# Bridge_Rectifier.net
KiCad netlist of a schematic drawn in Altium Designer
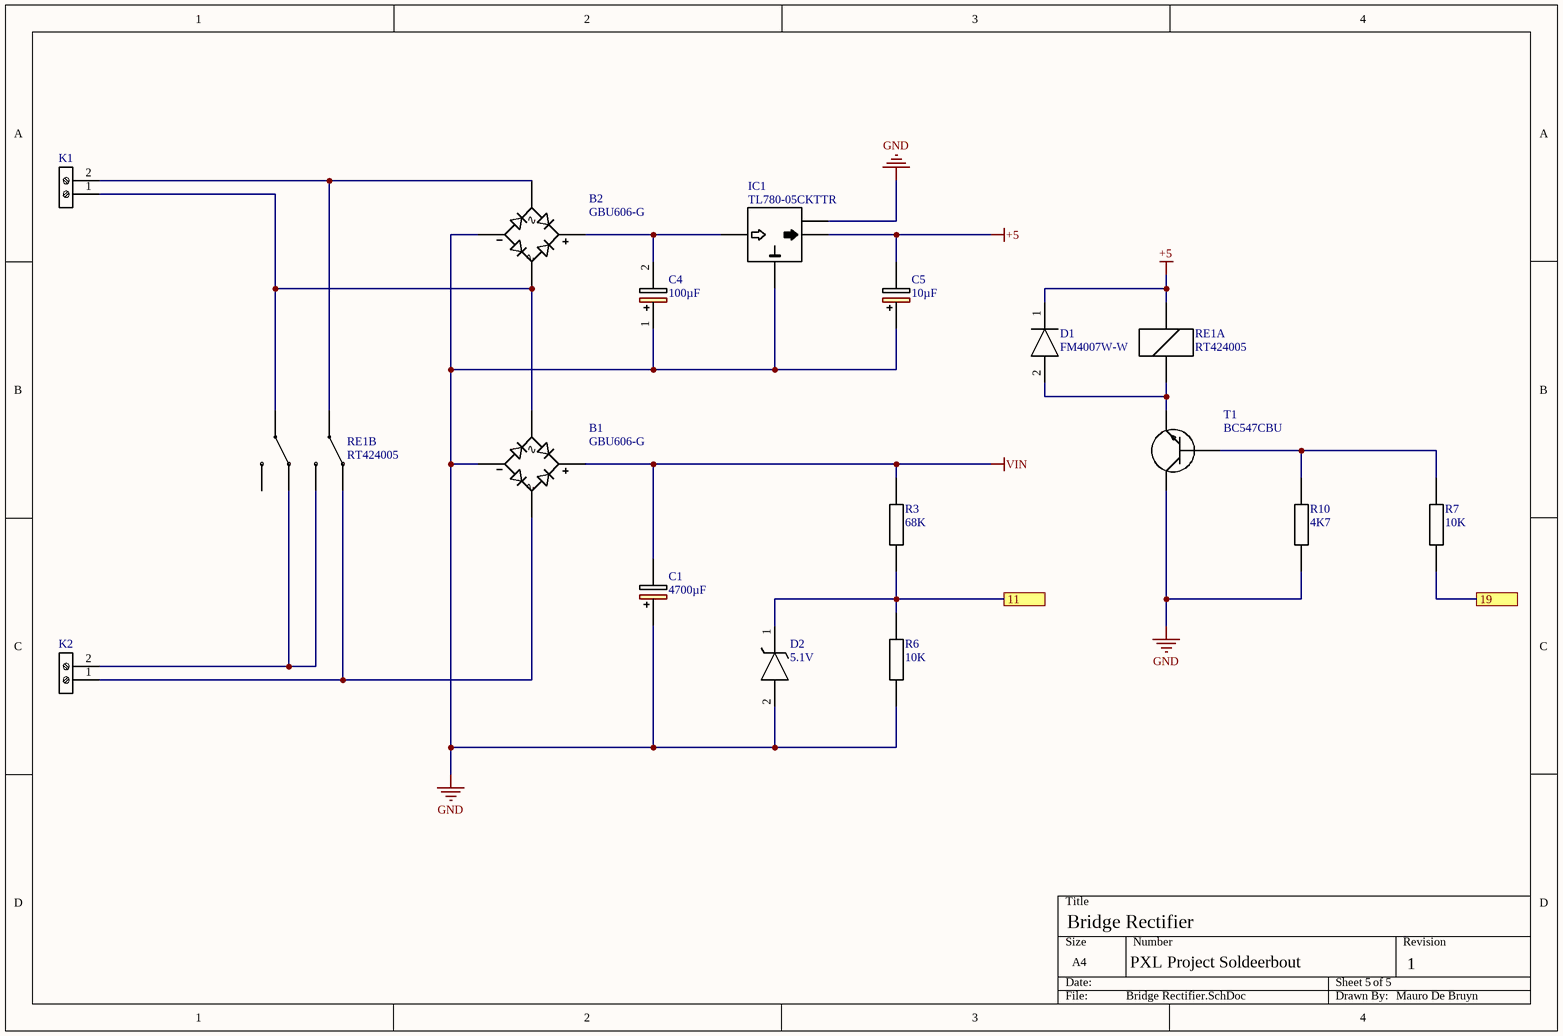
[diagram p0: Bridge Rectifier.SchDoc]

(export (version "E")
  (design (tool "Eeschema 10.0.6"))
  (components
    (comp (ref "B1")
      (value "GBU606-G")
      (footprint "SamacSys:GBU606G")
      (description "Bridge Rectifier")
      (libsource (lib "SamacSys") (part "GBU606-G"))
    )
    (comp (ref "B2")
      (value "GBU606-G")
      (footprint "SamacSys:GBU606G")
      (description "Bridge Rectifier")
      (libsource (lib "SamacSys") (part "GBU606-G"))
    )
    (comp (ref "C1")
      (value "4700µF")
      (footprint "SamacSys:CAPPRD750W80D1850H4150")
      (description "Capacitor Polarised")
      (fields
        (field (name "MOUSER2 PART NUMBER") "232-50PK4700MEFC18X4")
        (field (name "MANUFACTURER_PART_NUMBER") "50PK4700MEFC18X40")
      )
      (libsource (lib "SamacSys") (part "50PK4700MEFC18X40"))
    )
    (comp (ref "C4")
      (value "100µF")
      (footprint "SamacSys:CAPPRD350W60D825H1300")
      (description "Capacitor Polarised")
      (fields (field (name "MANUFACTURER_PART_NUMBER") "RGA101M1HBK-0811G"))
      (libsource (lib "SamacSys") (part "RGA101M1HBK-0811G"))
    )
    (comp (ref "C5")
      (value "10µF")
      (footprint "SamacSys:CAPPRD200W52D500H1250")
      (description "Capacitor Polarised")
      (fields
        (field (name "MOUSER2 PART NUMBER") "710-860020672010")
        (field (name "MANUFACTURER_PART_NUMBER") "860020672010")
      )
      (libsource (lib "SamacSys") (part "860020672010"))
    )
    (comp (ref "D1")
      (value "FM4007W-W")
      (footprint "SamacSys:DIOM5025X231N")
      (description "Bridge Rectifier")
      (fields (field (name "MOUSER2 PART NUMBER") "583-FM4007W-W"))
      (libsource (lib "SamacSys") (part "FM4007W-W"))
    )
    (comp (ref "D2")
      (value "5.1V")
      (footprint "SamacSys:SOD3716X135N")
      (description "Zener Diode")
      (fields
        (field (name "MOUSER2 PART NUMBER") "863-MMSZ4689T1G")
        (field (name "MANUFACTURER_PART_NUMBER") "MMSZ4689T1G")
      )
      (libsource (lib "SamacSys") (part "MMSZ4689T1G"))
    )
    (comp (ref "IC1")
      (value "TL780-05CKTTR")
      (footprint "SamacSys:TL78005CKTTR")
      (description "Integrated Circuit")
      (libsource (lib "SamacSys") (part "TL780-05CKTTR"))
    )
    (comp (ref "K1")
      (value "2 Pin Connector 1716020000")
      (footprint "SamacSys:1716020000")
      (description "Connector")
      (fields (field (name "MANUFACTURER_PART_NUMBER") "1716020000"))
      (libsource (lib "SamacSys") (part "2 Pin Connector 1716020000"))
    )
    (comp (ref "K2")
      (value "2 Pin Connector 1716020000")
      (footprint "SamacSys:1716020000")
      (description "Connector")
      (fields (field (name "MANUFACTURER_PART_NUMBER") "1716020000"))
      (libsource (lib "SamacSys") (part "2 Pin Connector 1716020000"))
    )
    (comp (ref "R3")
      (value "68K")
      (footprint "SamacSys:C0805")
      (description "Resistor")
      (fields (field (name "MANUFACTURER_PART_NUMBER") "C0805C391G3GACTU"))
      (libsource (lib "SamacSys") (part "0805"))
    )
    (comp (ref "R6")
      (value "10K")
      (footprint "SamacSys:C0805")
      (description "Resistor")
      (fields (field (name "MANUFACTURER_PART_NUMBER") "C0805C391G3GACTU"))
      (libsource (lib "SamacSys") (part "0805"))
    )
    (comp (ref "R7")
      (value "10K")
      (footprint "SamacSys:C0805")
      (description "Resistor")
      (fields (field (name "MANUFACTURER_PART_NUMBER") "C0805C391G3GACTU"))
      (libsource (lib "SamacSys") (part "0805"))
    )
    (comp (ref "R10")
      (value "4K7")
      (footprint "SamacSys:C0805")
      (description "Resistor")
      (fields (field (name "MANUFACTURER_PART_NUMBER") "C0805C391G3GACTU"))
      (libsource (lib "SamacSys") (part "0805"))
    )
    (comp (ref "RE1")
      (value "RT424005")
      (footprint "SamacSys:RT42")
      (description "Relay or Contactor")
      (fields (field (name "MOUSER2 PART NUMBER") "655-RT424005"))
      (libsource (lib "SamacSys") (part "RT424005"))
    )
    (comp (ref "T1")
      (value "BC547CBU")
      (footprint "SamacSys:BC547CBU")
      (description "Transistor BJT NPN")
      (libsource (lib "SamacSys") (part "BC547CBU"))
    )
  )
  (nets
    (net (code "1") (name "+5") (class "Default")
      (node (ref "C5") (pin "2") (pinfunction "-_2") (pintype "passive"))
      (node (ref "D1") (pin "1") (pinfunction "K_1") (pintype "passive"))
      (node (ref "IC1") (pin "3") (pinfunction "OUTPUT_3") (pintype "passive"))
      (node (ref "RE1") (pin "1") (pinfunction "A1_COIL_1") (pintype "passive"))
    )
    (net (code "2") (name "/11") (class "Default")
      (node (ref "D2") (pin "1") (pinfunction "K_1") (pintype "passive"))
      (node (ref "R3") (pin "1") (pinfunction "1_1") (pintype "passive"))
      (node (ref "R6") (pin "2") (pinfunction "2_2") (pintype "passive"))
    )
    (net (code "3") (name "/19") (class "Default")
      (node (ref "R7") (pin "1") (pinfunction "1_1") (pintype "passive"))
    )
    (net (code "4") (name "GND") (class "Default")
      (node (ref "B1") (pin "4") (pinfunction "-_4") (pintype "passive"))
      (node (ref "B2") (pin "4") (pinfunction "-_4") (pintype "passive"))
      (node (ref "C1") (pin "1") (pinfunction "+_1") (pintype "passive"))
      (node (ref "C4") (pin "1") (pinfunction "+_1") (pintype "passive"))
      (node (ref "C5") (pin "1") (pinfunction "+_1") (pintype "passive"))
      (node (ref "D2") (pin "2") (pinfunction "A_2") (pintype "passive"))
      (node (ref "IC1") (pin "2") (pinfunction "COMMON_1_2") (pintype "passive"))
      (node (ref "IC1") (pin "4") (pinfunction "COMMON_2_4") (pintype "passive"))
      (node (ref "R10") (pin "1") (pinfunction "1_1") (pintype "passive"))
      (node (ref "R6") (pin "1") (pinfunction "1_1") (pintype "passive"))
      (node (ref "T1") (pin "1") (pinfunction "C_1") (pintype "passive"))
    )
    (net (code "5") (name "Net-(B1-~_1)") (class "Default")
      (node (ref "B1") (pin "2") (pinfunction "~_1_2") (pintype "passive"))
      (node (ref "K2") (pin "1") (pinfunction "1_1") (pintype "passive"))
      (node (ref "RE1") (pin "7") (pinfunction "22_NC_7") (pintype "passive"))
    )
    (net (code "6") (name "Net-(B1-~_2)") (class "Default")
      (node (ref "B1") (pin "3") (pinfunction "~_2_3") (pintype "passive"))
      (node (ref "B2") (pin "2") (pinfunction "~_1_2") (pintype "passive"))
      (node (ref "K1") (pin "1") (pinfunction "1_1") (pintype "passive"))
      (node (ref "RE1") (pin "3") (pinfunction "11_COM_3") (pintype "passive"))
    )
    (net (code "7") (name "Net-(B2-+)") (class "Default")
      (node (ref "B2") (pin "1") (pinfunction "+_1") (pintype "passive"))
      (node (ref "C4") (pin "2") (pinfunction "-_2") (pintype "passive"))
      (node (ref "IC1") (pin "1") (pinfunction "INPUT_1") (pintype "passive"))
    )
    (net (code "8") (name "Net-(B2-~_2)") (class "Default")
      (node (ref "B2") (pin "3") (pinfunction "~_2_3") (pintype "passive"))
      (node (ref "K1") (pin "2") (pinfunction "2_2") (pintype "passive"))
      (node (ref "RE1") (pin "6") (pinfunction "21_COM_6") (pintype "passive"))
    )
    (net (code "9") (name "Net-(D1-A)") (class "Default")
      (node (ref "D1") (pin "2") (pinfunction "A_2") (pintype "passive"))
      (node (ref "RE1") (pin "8") (pinfunction "A2_COIL_8") (pintype "passive"))
      (node (ref "T1") (pin "3") (pinfunction "E_3") (pintype "passive"))
    )
    (net (code "10") (name "Net-(RE1B-12_NC)") (class "Default")
      (node (ref "K2") (pin "2") (pinfunction "2_2") (pintype "passive"))
      (node (ref "RE1") (pin "2") (pinfunction "12_NC_2") (pintype "passive"))
      (node (ref "RE1") (pin "5") (pinfunction "24_NO_5") (pintype "passive"))
    )
    (net (code "11") (name "Net-(T1-B)") (class "Default")
      (node (ref "R10") (pin "2") (pinfunction "2_2") (pintype "passive"))
      (node (ref "R7") (pin "2") (pinfunction "2_2") (pintype "passive"))
      (node (ref "T1") (pin "2") (pinfunction "B_2") (pintype "passive"))
    )
    (net (code "12") (name "VIN") (class "Default")
      (node (ref "B1") (pin "1") (pinfunction "+_1") (pintype "passive"))
      (node (ref "C1") (pin "2") (pinfunction "-_2") (pintype "passive"))
      (node (ref "R3") (pin "2") (pinfunction "2_2") (pintype "passive"))
    )
    (net (code "13") (name "unconnected-(RE1B-14_NO-Pad4)") (class "Default")
      (node (ref "RE1") (pin "4") (pinfunction "14_NO_4") (pintype "passive"))
    )
  )
)
